# connectors.net
KiCad netlist of a schematic drawn in Altium Designer
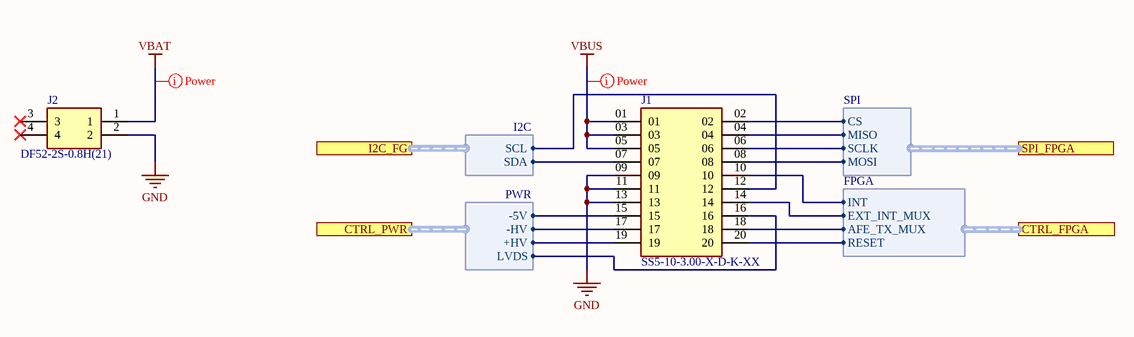
[diagram p0: connectors.SchDoc]

(export (version "E")
  (design (tool "Eeschema 10.0.6"))
  (components
    (comp (ref "J1")
      (value "SS5-10-3.00-X-D-K-XX")
      (footprint "SAMTEC_SS5-10-3.00-X-D-K-XX")
      (description "0.50mm Socket Strip Assembly")
      (fields (field (name "MF") "Samtec Inc."))
      (libsource (lib "SS5-10-3.00-X-D-K-XX") (part "SS5-10-3.00-X-D-K-XX"))
    )
    (comp (ref "J2")
      (value "DF52-2S-0.8H(21)")
      (footprint "SamacSys:DF522S08H21")
      (description "Connector")
      (fields (field (name "MOUSER PART NUMBER") "798-DF52-2S-0.8H21"))
      (libsource (lib "*") (part "DF52-2S-0.8H_21_"))
    )
  )
  (nets
    (net (code "5") (name "/+HV") (class "Default")
      (node (ref "J1") (pin "19") (pinfunction "19_19") (pintype "passive"))
    )
    (net (code "6") (name "/-5V") (class "Default")
      (node (ref "J1") (pin "15") (pinfunction "15_15") (pintype "passive"))
    )
    (net (code "7") (name "/-HV") (class "Default")
      (node (ref "J1") (pin "17") (pinfunction "17_17") (pintype "passive"))
    )
    (net (code "8") (name "/AFE_TX_MUX") (class "Default")
      (node (ref "J1") (pin "18") (pinfunction "18_18") (pintype "passive"))
    )
    (net (code "9") (name "/CS") (class "Default")
      (node (ref "J1") (pin "02") (pinfunction "02_02") (pintype "passive"))
    )
    (net (code "10") (name "/EXT_INT_MUX") (class "Default")
      (node (ref "J1") (pin "14") (pinfunction "14_14") (pintype "passive"))
    )
    (net (code "11") (name "/INT") (class "Default")
      (node (ref "J1") (pin "10") (pinfunction "10_10") (pintype "passive"))
    )
    (net (code "12") (name "/LVDS") (class "Default")
      (node (ref "J1") (pin "16") (pinfunction "16_16") (pintype "passive"))
    )
    (net (code "13") (name "/MISO") (class "Default")
      (node (ref "J1") (pin "04") (pinfunction "04_04") (pintype "passive"))
    )
    (net (code "14") (name "/MOSI") (class "Default")
      (node (ref "J1") (pin "08") (pinfunction "08_08") (pintype "passive"))
    )
    (net (code "15") (name "/RESET") (class "Default")
      (node (ref "J1") (pin "20") (pinfunction "20_20") (pintype "passive"))
    )
    (net (code "16") (name "/SCL") (class "Default")
      (node (ref "J1") (pin "12") (pinfunction "12_12") (pintype "passive"))
    )
    (net (code "17") (name "/SCLK") (class "Default")
      (node (ref "J1") (pin "06") (pinfunction "06_06") (pintype "passive"))
    )
    (net (code "18") (name "/SDA") (class "Default")
      (node (ref "J1") (pin "07") (pinfunction "07_07") (pintype "passive"))
    )
    (net (code "23") (name "GND") (class "Default")
      (node (ref "J1") (pin "09") (pinfunction "09_09") (pintype "passive"))
      (node (ref "J1") (pin "11") (pinfunction "11_11") (pintype "passive"))
      (node (ref "J1") (pin "13") (pinfunction "13_13") (pintype "passive"))
      (node (ref "J2") (pin "2") (pinfunction "2_2") (pintype "passive"))
    )
    (net (code "24") (name "VBAT") (class "Default")
      (node (ref "J2") (pin "1") (pinfunction "1_1") (pintype "passive"))
    )
    (net (code "25") (name "VBUS") (class "Default")
      (node (ref "J1") (pin "01") (pinfunction "01_01") (pintype "passive"))
      (node (ref "J1") (pin "03") (pinfunction "03_03") (pintype "passive"))
      (node (ref "J1") (pin "05") (pinfunction "05_05") (pintype "passive"))
    )
    (net (code "26") (name "unconnected-(J2-Pad3)") (class "Default")
      (node (ref "J2") (pin "3") (pinfunction "3_3") (pintype "passive+no_connect"))
    )
    (net (code "27") (name "unconnected-(J2-Pad4)") (class "Default")
      (node (ref "J2") (pin "4") (pinfunction "4_4") (pintype "passive+no_connect"))
    )
  )
)
